# Laser_Array_CPU.net
KiCad netlist of a schematic drawn in EAGLE
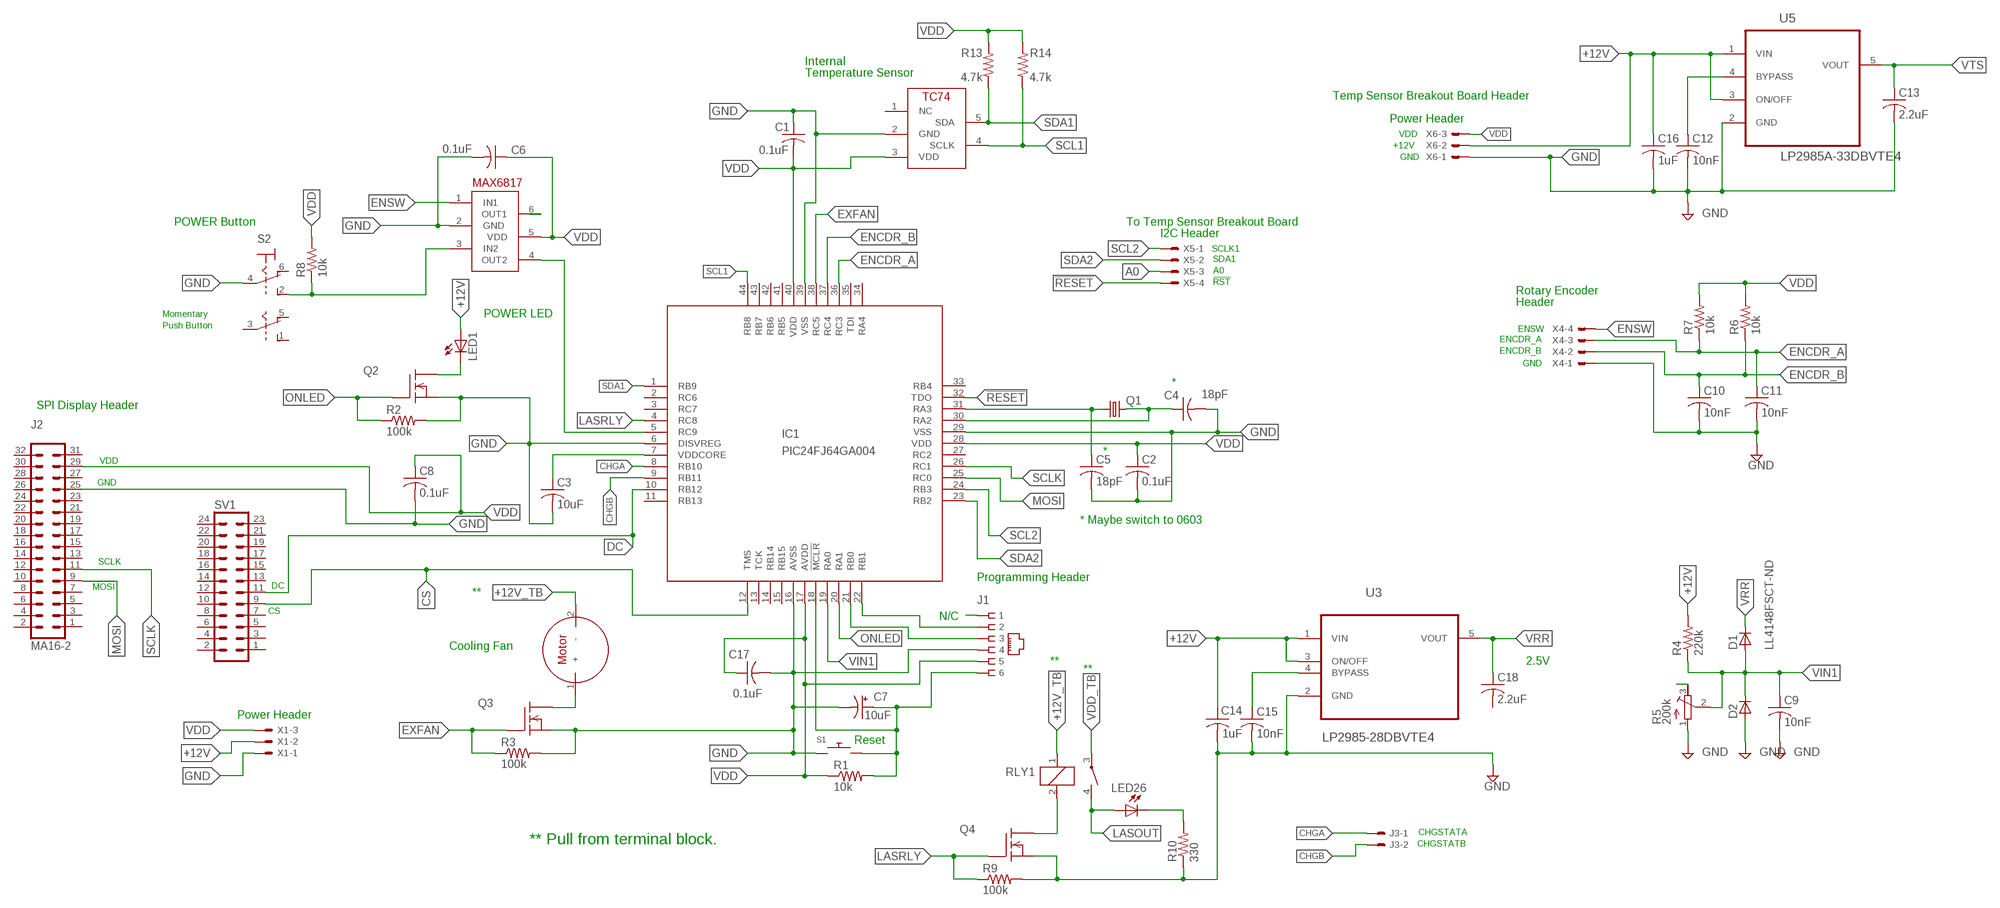
[diagram p0: schematic, sheet 1]

(export (version "E")
  (design (tool "Eeschema 10.0.6"))
  (components
    (comp (ref "C1")
      (value "0.1uF")
      (footprint "eagle-import:C0805")
      (libsource (lib "eagle-import") (part "C-USC0805"))
    )
    (comp (ref "C2")
      (value "0.1uF")
      (footprint "eagle-import:C0805")
      (libsource (lib "eagle-import") (part "C-USC0805"))
    )
    (comp (ref "C3")
      (value "10uF")
      (footprint "eagle-import:C0805")
      (libsource (lib "eagle-import") (part "C-USC0805"))
    )
    (comp (ref "C4")
      (value "18pF")
      (footprint "eagle-import:C0805")
      (libsource (lib "eagle-import") (part "C-USC0805"))
    )
    (comp (ref "C5")
      (value "18pF")
      (footprint "eagle-import:C0805")
      (libsource (lib "eagle-import") (part "C-USC0805"))
    )
    (comp (ref "C6")
      (value "0.1uF")
      (footprint "eagle-import:C0805")
      (libsource (lib "eagle-import") (part "C-USC0805"))
    )
    (comp (ref "C7")
      (value "10uF")
      (footprint "eagle-import:CAP3X3")
      (libsource (lib "eagle-import") (part "CAP3X3"))
    )
    (comp (ref "C8")
      (value "0.1uF")
      (footprint "eagle-import:C0805")
      (libsource (lib "eagle-import") (part "C-USC0805"))
    )
    (comp (ref "C9")
      (value "10nF")
      (footprint "eagle-import:C0805")
      (libsource (lib "eagle-import") (part "C-USC0805"))
    )
    (comp (ref "C10")
      (value "10nF")
      (footprint "eagle-import:C0805")
      (libsource (lib "eagle-import") (part "C-USC0805"))
    )
    (comp (ref "C11")
      (value "10nF")
      (footprint "eagle-import:C0805")
      (libsource (lib "eagle-import") (part "C-USC0805"))
    )
    (comp (ref "C12")
      (value "10nF")
      (footprint "eagle-import:C0805")
      (libsource (lib "eagle-import") (part "C-USC0805"))
    )
    (comp (ref "C13")
      (value "2.2uF")
      (footprint "eagle-import:C0805")
      (libsource (lib "eagle-import") (part "C-USC0805"))
    )
    (comp (ref "C14")
      (value "1uF")
      (footprint "eagle-import:C0805")
      (libsource (lib "eagle-import") (part "C-USC0805"))
    )
    (comp (ref "C15")
      (value "10nF")
      (footprint "eagle-import:C0805")
      (libsource (lib "eagle-import") (part "C-USC0805"))
    )
    (comp (ref "C16")
      (value "1uF")
      (footprint "eagle-import:C0805")
      (libsource (lib "eagle-import") (part "C-USC0805"))
    )
    (comp (ref "C17")
      (value "0.1uF")
      (footprint "eagle-import:C0805")
      (libsource (lib "eagle-import") (part "C-USC0805"))
    )
    (comp (ref "C18")
      (value "2.2uF")
      (footprint "eagle-import:C0805")
      (libsource (lib "eagle-import") (part "C-USC0805"))
    )
    (comp (ref "D1")
      (value "LL4148FSCT-ND")
      (footprint "eagle-import:SOD80")
      (libsource (lib "eagle-import") (part "D-SOD-80"))
    )
    (comp (ref "D2")
      (value "LL4148FSCT-ND")
      (footprint "eagle-import:SOD80")
      (libsource (lib "eagle-import") (part "D-SOD-80"))
    )
    (comp (ref "IC1")
      (value "PIC24FJ64GA004")
      (footprint "eagle-import:TQFP44")
      (fields (field (name "MPN") "PIC24FJ64GA004-E/PT"))
      (libsource (lib "eagle-import") (part "PIC24FJ64GA004"))
    )
    (comp (ref "J1")
      (value "RJ_25")
      (footprint "eagle-import:RJ11-NO_SHIELD")
      (libsource (lib "eagle-import") (part "RJ_25"))
    )
    (comp (ref "J2")
      (value "MA16-2")
      (footprint "eagle-import:MA16-2")
      (libsource (lib "eagle-import") (part "MA16-2"))
    )
    (comp (ref "J3")
      (value "22-23-2021")
      (footprint "eagle-import:22-23-2021")
      (fields (field (name "MF") "MOLEX"))
      (libsource (lib "eagle-import") (part "22-23-2021"))
    )
    (comp (ref "LED1")
      (value "LEDA5MM")
      (footprint "eagle-import:LED5MM")
      (libsource (lib "eagle-import") (part "LEDA5MM"))
    )
    (comp (ref "LED26")
      (value "LEDA5MM")
      (footprint "eagle-import:LED5MM")
      (libsource (lib "eagle-import") (part "LEDA5MM"))
    )
    (comp (ref "M1")
      (value "MOTOR")
      (footprint "eagle-import:22-23-2021")
      (libsource (lib "eagle-import") (part "MOTOR"))
    )
    (comp (ref "Q1")
      (value "CRYSTALSM49")
      (footprint "eagle-import:SM49")
      (libsource (lib "eagle-import") (part "CRYSTALSM49"))
    )
    (comp (ref "Q2")
      (value "QS5U34CT-ND_MOSFET_N_CHANNEL")
      (footprint "eagle-import:SOT23-5L")
      (libsource (lib "eagle-import") (part "QS5U34CT-ND_MOSFET_N_CHANNEL"))
    )
    (comp (ref "Q3")
      (value "QS5U34CT-ND_MOSFET_N_CHANNEL")
      (footprint "eagle-import:SOT23-5L")
      (libsource (lib "eagle-import") (part "QS5U34CT-ND_MOSFET_N_CHANNEL"))
    )
    (comp (ref "Q4")
      (value "QS5U34CT-ND_MOSFET_N_CHANNEL")
      (footprint "eagle-import:SOT23-5L")
      (libsource (lib "eagle-import") (part "QS5U34CT-ND_MOSFET_N_CHANNEL"))
    )
    (comp (ref "R1")
      (value "10k")
      (footprint "eagle-import:R0805")
      (libsource (lib "eagle-import") (part "R-US_R0805"))
    )
    (comp (ref "R2")
      (value "100k")
      (footprint "eagle-import:R0805")
      (libsource (lib "eagle-import") (part "R-US_R0805"))
    )
    (comp (ref "R3")
      (value "100k")
      (footprint "eagle-import:R0805")
      (libsource (lib "eagle-import") (part "R-US_R0805"))
    )
    (comp (ref "R4")
      (value "220k")
      (footprint "eagle-import:M0805")
      (libsource (lib "eagle-import") (part "R-US_M0805"))
    )
    (comp (ref "R5")
      (value "200k")
      (footprint "eagle-import:RTRIM3224X")
      (libsource (lib "eagle-import") (part "R-TRIMM3224X"))
    )
    (comp (ref "R6")
      (value "10k")
      (footprint "eagle-import:M0805")
      (libsource (lib "eagle-import") (part "R-US_M0805"))
    )
    (comp (ref "R7")
      (value "10k")
      (footprint "eagle-import:M0805")
      (libsource (lib "eagle-import") (part "R-US_M0805"))
    )
    (comp (ref "R8")
      (value "10k")
      (footprint "eagle-import:R0805")
      (libsource (lib "eagle-import") (part "R-US_R0805"))
    )
    (comp (ref "R9")
      (value "100k")
      (footprint "eagle-import:R0805")
      (libsource (lib "eagle-import") (part "R-US_R0805"))
    )
    (comp (ref "R10")
      (value "330")
      (footprint "eagle-import:R0805")
      (libsource (lib "eagle-import") (part "R-US_R0805"))
    )
    (comp (ref "R13")
      (value "4.7k")
      (footprint "eagle-import:M0805")
      (libsource (lib "eagle-import") (part "R-US_M0805"))
    )
    (comp (ref "R14")
      (value "4.7k")
      (footprint "eagle-import:M0805")
      (libsource (lib "eagle-import") (part "R-US_M0805"))
    )
    (comp (ref "RLY1")
      (value "RELAY_SPST")
      (footprint "eagle-import:RELAY_SPST")
      (libsource (lib "eagle-import") (part "RELAY_SPST"))
    )
    (comp (ref "S1")
      (value "TACT_PB")
      (footprint "eagle-import:PUSHBUTTON_SMD_SJ")
      (libsource (lib "eagle-import") (part "TACT_PB"))
    )
    (comp (ref "S2")
      (value "DPDT_TOGGLE")
      (footprint "eagle-import:22-23-2061")
      (libsource (lib "eagle-import") (part "DPDT_TOGGLE"))
    )
    (comp (ref "S3")
      (value "TC74")
      (footprint "eagle-import:SOT23-5L")
      (libsource (lib "eagle-import") (part "TC74"))
    )
    (comp (ref "SV1")
      (value "MA12-2")
      (footprint "eagle-import:MA12-2")
      (libsource (lib "eagle-import") (part "MA12-2"))
    )
    (comp (ref "U2")
      (value "MAX6817")
      (footprint "eagle-import:SOT23-6")
      (libsource (lib "eagle-import") (part "MAX6817"))
    )
    (comp (ref "U3")
      (value "LP2985-28DBVTE4")
      (footprint "eagle-import:SOT95P280X145-5N")
      (libsource (lib "eagle-import") (part "LP2985-28DBVTE4"))
    )
    (comp (ref "U5")
      (value "LP2985A-33DBVTE4")
      (footprint "eagle-import:SOT95P280X145-5N")
      (libsource (lib "eagle-import") (part "LP2985A-33DBVTE4"))
    )
    (comp (ref "X1")
      (value "22-23-2031")
      (footprint "eagle-import:22-23-2031")
      (fields (field (name "MF") "MOLEX"))
      (libsource (lib "eagle-import") (part "22-23-2031"))
    )
    (comp (ref "X4")
      (value "22-23-2041")
      (footprint "eagle-import:22-23-2041")
      (fields (field (name "MF") "MOLEX"))
      (libsource (lib "eagle-import") (part "22-23-2041"))
    )
    (comp (ref "X5")
      (value "22-23-2041")
      (footprint "eagle-import:22-23-2041")
      (fields (field (name "MF") "MOLEX"))
      (libsource (lib "eagle-import") (part "22-23-2041"))
    )
    (comp (ref "X6")
      (value "22-23-2031")
      (footprint "eagle-import:22-23-2031")
      (fields (field (name "MF") "MOLEX"))
      (libsource (lib "eagle-import") (part "22-23-2031"))
    )
  )
  (nets
    (net (code "1") (name "+12V") (class "Default")
      (node (ref "C14") (pin "1") (pinfunction "1_1") (pintype "passive"))
      (node (ref "C16") (pin "1") (pinfunction "1_1") (pintype "passive"))
      (node (ref "LED1") (pin "A") (pinfunction "A_A") (pintype "passive"))
      (node (ref "R4") (pin "2") (pinfunction "2_2") (pintype "passive"))
      (node (ref "U3") (pin "1") (pinfunction "VIN_1") (pintype "power_in"))
      (node (ref "U3") (pin "3") (pinfunction "ON/OFF_3") (pintype "input"))
      (node (ref "U5") (pin "1") (pinfunction "VIN_1") (pintype "power_in"))
      (node (ref "U5") (pin "3") (pinfunction "ON/OFF_3") (pintype "input"))
      (node (ref "X1") (pin "2") (pinfunction "S_2") (pintype "passive"))
      (node (ref "X6") (pin "2") (pinfunction "S_2") (pintype "passive"))
    )
    (net (code "2") (name "+12V_TB") (class "Default")
      (node (ref "M1") (pin "2") (pinfunction "-_2") (pintype "bidirectional"))
      (node (ref "RLY1") (pin "1") (pinfunction "1_1") (pintype "passive"))
    )
    (net (code "3") (name "/~{RESET}") (class "Default")
      (node (ref "IC1") (pin "32") (pinfunction "TDO_32") (pintype "output"))
      (node (ref "X5") (pin "4") (pinfunction "S_4") (pintype "passive"))
    )
    (net (code "4") (name "A0") (class "Default")
      (node (ref "X5") (pin "3") (pinfunction "S_3") (pintype "passive"))
    )
    (net (code "5") (name "CHGA") (class "Default")
      (node (ref "IC1") (pin "8") (pinfunction "RB10_8") (pintype "bidirectional"))
      (node (ref "J3") (pin "1") (pinfunction "S_1") (pintype "passive"))
    )
    (net (code "6") (name "CHGB") (class "Default")
      (node (ref "IC1") (pin "9") (pinfunction "RB11_9") (pintype "bidirectional"))
      (node (ref "J3") (pin "2") (pinfunction "S_2") (pintype "passive"))
    )
    (net (code "7") (name "CS") (class "Default")
      (node (ref "IC1") (pin "12") (pinfunction "TMS_12") (pintype "input"))
      (node (ref "SV1") (pin "9") (pinfunction "9_9") (pintype "passive"))
    )
    (net (code "8") (name "DC") (class "Default")
      (node (ref "IC1") (pin "10") (pinfunction "RB12_10") (pintype "bidirectional"))
      (node (ref "SV1") (pin "11") (pinfunction "11_11") (pintype "passive"))
    )
    (net (code "9") (name "ENCDR_A") (class "Default")
      (node (ref "C11") (pin "1") (pinfunction "1_1") (pintype "passive"))
      (node (ref "IC1") (pin "36") (pinfunction "RC3_36") (pintype "bidirectional"))
      (node (ref "R7") (pin "1") (pinfunction "1_1") (pintype "passive"))
      (node (ref "X4") (pin "3") (pinfunction "S_3") (pintype "passive"))
    )
    (net (code "10") (name "ENCDR_B") (class "Default")
      (node (ref "C10") (pin "1") (pinfunction "1_1") (pintype "passive"))
      (node (ref "IC1") (pin "37") (pinfunction "RC4_37") (pintype "bidirectional"))
      (node (ref "R6") (pin "1") (pinfunction "1_1") (pintype "passive"))
      (node (ref "X4") (pin "2") (pinfunction "S_2") (pintype "passive"))
    )
    (net (code "11") (name "ENSW") (class "Default")
      (node (ref "U2") (pin "1") (pinfunction "IN1_1") (pintype "input"))
      (node (ref "X4") (pin "4") (pinfunction "S_4") (pintype "passive"))
    )
    (net (code "12") (name "EXFAN") (class "Default")
      (node (ref "IC1") (pin "38") (pinfunction "RC5_38") (pintype "bidirectional"))
      (node (ref "Q3") (pin "1") (pinfunction "G_1") (pintype "passive"))
      (node (ref "R3") (pin "1") (pinfunction "1_1") (pintype "passive"))
    )
    (net (code "13") (name "GND") (class "Default")
      (node (ref "C1") (pin "1") (pinfunction "1_1") (pintype "passive"))
      (node (ref "C10") (pin "2") (pinfunction "2_2") (pintype "passive"))
      (node (ref "C11") (pin "2") (pinfunction "2_2") (pintype "passive"))
      (node (ref "C12") (pin "2") (pinfunction "2_2") (pintype "passive"))
      (node (ref "C13") (pin "2") (pinfunction "2_2") (pintype "passive"))
      (node (ref "C14") (pin "2") (pinfunction "2_2") (pintype "passive"))
      (node (ref "C15") (pin "2") (pinfunction "2_2") (pintype "passive"))
      (node (ref "C16") (pin "2") (pinfunction "2_2") (pintype "passive"))
      (node (ref "C17") (pin "2") (pinfunction "2_2") (pintype "passive"))
      (node (ref "C2") (pin "2") (pinfunction "2_2") (pintype "passive"))
      (node (ref "C3") (pin "2") (pinfunction "2_2") (pintype "passive"))
      (node (ref "C4") (pin "2") (pinfunction "2_2") (pintype "passive"))
      (node (ref "C5") (pin "2") (pinfunction "2_2") (pintype "passive"))
      (node (ref "C6") (pin "2") (pinfunction "2_2") (pintype "passive"))
      (node (ref "C7") (pin "-") (pinfunction "-_-") (pintype "passive"))
      (node (ref "C8") (pin "2") (pinfunction "2_2") (pintype "passive"))
      (node (ref "C9") (pin "2") (pinfunction "2_2") (pintype "passive"))
      (node (ref "D2") (pin "2") (pinfunction "A_2") (pintype "passive"))
      (node (ref "IC1") (pin "16") (pinfunction "AVSS_16") (pintype "power_in"))
      (node (ref "IC1") (pin "29") (pinfunction "VSS_29") (pintype "power_in"))
      (node (ref "IC1") (pin "39") (pinfunction "VSS_39") (pintype "power_in"))
      (node (ref "IC1") (pin "6") (pinfunction "DISVREG_6") (pintype "passive"))
      (node (ref "J1") (pin "4") (pinfunction "4_4") (pintype "passive"))
      (node (ref "J2") (pin "25") (pinfunction "25_25") (pintype "passive"))
      (node (ref "Q2") (pin "2") (pinfunction "S_2") (pintype "passive"))
      (node (ref "Q3") (pin "2") (pinfunction "S_2") (pintype "passive"))
      (node (ref "Q4") (pin "2") (pinfunction "S_2") (pintype "passive"))
      (node (ref "R10") (pin "1") (pinfunction "1_1") (pintype "passive"))
      (node (ref "R2") (pin "2") (pinfunction "2_2") (pintype "passive"))
      (node (ref "R3") (pin "2") (pinfunction "2_2") (pintype "passive"))
      (node (ref "R5") (pin "1") (pinfunction "A_1") (pintype "passive"))
      (node (ref "R9") (pin "2") (pinfunction "2_2") (pintype "passive"))
      (node (ref "S1") (pin "1") (pinfunction "1_1") (pintype "passive"))
      (node (ref "S1") (pin "2") (pinfunction "1_2") (pintype "passive"))
      (node (ref "S2") (pin "4") (pinfunction "P_4") (pintype "passive"))
      (node (ref "S3") (pin "2") (pinfunction "GND_2") (pintype "bidirectional"))
      (node (ref "U2") (pin "2") (pinfunction "GND_2") (pintype "power_in"))
      (node (ref "U3") (pin "2") (pinfunction "GND_2") (pintype "passive"))
      (node (ref "U5") (pin "2") (pinfunction "GND_2") (pintype "passive"))
      (node (ref "X1") (pin "1") (pinfunction "S_1") (pintype "passive"))
      (node (ref "X4") (pin "1") (pinfunction "S_1") (pintype "passive"))
      (node (ref "X6") (pin "1") (pinfunction "S_1") (pintype "passive"))
    )
    (net (code "14") (name "LASOUT") (class "Default")
      (node (ref "LED26") (pin "A") (pinfunction "A_A") (pintype "passive"))
      (node (ref "RLY1") (pin "4") (pinfunction "S_4") (pintype "passive"))
    )
    (net (code "15") (name "LASRLY") (class "Default")
      (node (ref "IC1") (pin "4") (pinfunction "RC8_4") (pintype "bidirectional"))
      (node (ref "Q4") (pin "1") (pinfunction "G_1") (pintype "passive"))
      (node (ref "R9") (pin "1") (pinfunction "1_1") (pintype "passive"))
    )
    (net (code "16") (name "MOSI") (class "Default")
      (node (ref "IC1") (pin "25") (pinfunction "RC0_25") (pintype "bidirectional"))
      (node (ref "J2") (pin "9") (pinfunction "9_9") (pintype "passive"))
    )
    (net (code "17") (name "Net-(IC1-RA2)") (class "Default")
      (node (ref "C4") (pin "1") (pinfunction "1_1") (pintype "passive"))
      (node (ref "IC1") (pin "30") (pinfunction "RA2_30") (pintype "bidirectional"))
      (node (ref "Q1") (pin "2") (pinfunction "2_2") (pintype "passive"))
    )
    (net (code "18") (name "Net-(IC1-RA3)") (class "Default")
      (node (ref "C5") (pin "1") (pinfunction "1_1") (pintype "passive"))
      (node (ref "IC1") (pin "31") (pinfunction "RA3_31") (pintype "bidirectional"))
      (node (ref "Q1") (pin "1") (pinfunction "1_1") (pintype "passive"))
    )
    (net (code "19") (name "Net-(IC1-RB0)") (class "Default")
      (node (ref "IC1") (pin "21") (pinfunction "RB0_21") (pintype "bidirectional"))
      (node (ref "J1") (pin "3") (pinfunction "3_3") (pintype "passive"))
    )
    (net (code "20") (name "Net-(IC1-RB1)") (class "Default")
      (node (ref "IC1") (pin "22") (pinfunction "RB1_22") (pintype "bidirectional"))
      (node (ref "J1") (pin "2") (pinfunction "2_2") (pintype "passive"))
    )
    (net (code "21") (name "Net-(IC1-RC9)") (class "Default")
      (node (ref "IC1") (pin "5") (pinfunction "RC9_5") (pintype "bidirectional"))
      (node (ref "U2") (pin "4") (pinfunction "OUT2_4") (pintype "output"))
    )
    (net (code "22") (name "Net-(IC1-VDDCORE)") (class "Default")
      (node (ref "C3") (pin "1") (pinfunction "1_1") (pintype "passive"))
      (node (ref "IC1") (pin "7") (pinfunction "VDDCORE_7") (pintype "power_in"))
    )
    (net (code "23") (name "Net-(IC1-~{MCLR})") (class "Default")
      (node (ref "C7") (pin "+") (pinfunction "+_+") (pintype "passive"))
      (node (ref "IC1") (pin "18") (pinfunction "~{MCLR}_18") (pintype "bidirectional"))
      (node (ref "J1") (pin "6") (pinfunction "6_6") (pintype "passive"))
      (node (ref "R1") (pin "2") (pinfunction "2_2") (pintype "passive"))
      (node (ref "S1") (pin "3") (pinfunction "2_3") (pintype "passive"))
      (node (ref "S1") (pin "4") (pinfunction "2_4") (pintype "passive"))
    )
    (net (code "24") (name "Net-(LED1-C)") (class "Default")
      (node (ref "LED1") (pin "K") (pinfunction "C_K") (pintype "passive"))
      (node (ref "Q2") (pin "5") (pinfunction "D_5") (pintype "passive"))
    )
    (net (code "25") (name "Net-(LED26-C)") (class "Default")
      (node (ref "LED26") (pin "K") (pinfunction "C_K") (pintype "passive"))
      (node (ref "R10") (pin "2") (pinfunction "2_2") (pintype "passive"))
    )
    (net (code "26") (name "Net-(M1-+)") (class "Default")
      (node (ref "M1") (pin "1") (pinfunction "+_1") (pintype "bidirectional"))
      (node (ref "Q3") (pin "5") (pinfunction "D_5") (pintype "passive"))
    )
    (net (code "27") (name "Net-(Q4-D)") (class "Default")
      (node (ref "Q4") (pin "5") (pinfunction "D_5") (pintype "passive"))
      (node (ref "RLY1") (pin "2") (pinfunction "2_2") (pintype "passive"))
    )
    (net (code "28") (name "Net-(S2-S)") (class "Default")
      (node (ref "R8") (pin "1") (pinfunction "1_1") (pintype "passive"))
      (node (ref "S2") (pin "2") (pinfunction "S_2") (pintype "passive"))
      (node (ref "U2") (pin "3") (pinfunction "IN2_3") (pintype "input"))
    )
    (net (code "29") (name "Net-(U3-BYPASS)") (class "Default")
      (node (ref "C15") (pin "1") (pinfunction "1_1") (pintype "passive"))
      (node (ref "U3") (pin "4") (pinfunction "BYPASS_4") (pintype "input"))
    )
    (net (code "30") (name "Net-(U5-BYPASS)") (class "Default")
      (node (ref "C12") (pin "1") (pinfunction "1_1") (pintype "passive"))
      (node (ref "U5") (pin "4") (pinfunction "BYPASS_4") (pintype "input"))
    )
    (net (code "31") (name "ONLED") (class "Default")
      (node (ref "IC1") (pin "20") (pinfunction "RA1_20") (pintype "bidirectional"))
      (node (ref "Q2") (pin "1") (pinfunction "G_1") (pintype "passive"))
      (node (ref "R2") (pin "1") (pinfunction "1_1") (pintype "passive"))
    )
    (net (code "32") (name "SCL1") (class "Default")
      (node (ref "IC1") (pin "44") (pinfunction "RB8_44") (pintype "bidirectional"))
      (node (ref "R14") (pin "1") (pinfunction "1_1") (pintype "passive"))
      (node (ref "S3") (pin "4") (pinfunction "SCLK_4") (pintype "bidirectional"))
    )
    (net (code "33") (name "SCL2") (class "Default")
      (node (ref "IC1") (pin "24") (pinfunction "RB3_24") (pintype "bidirectional"))
      (node (ref "X5") (pin "1") (pinfunction "S_1") (pintype "passive"))
    )
    (net (code "34") (name "SCLK") (class "Default")
      (node (ref "IC1") (pin "26") (pinfunction "RC1_26") (pintype "bidirectional"))
      (node (ref "J2") (pin "11") (pinfunction "11_11") (pintype "passive"))
    )
    (net (code "35") (name "SDA1") (class "Default")
      (node (ref "IC1") (pin "1") (pinfunction "RB9_1") (pintype "bidirectional"))
      (node (ref "R13") (pin "1") (pinfunction "1_1") (pintype "passive"))
      (node (ref "S3") (pin "5") (pinfunction "SDA_5") (pintype "bidirectional"))
    )
    (net (code "36") (name "SDA2") (class "Default")
      (node (ref "IC1") (pin "23") (pinfunction "RB2_23") (pintype "bidirectional"))
      (node (ref "X5") (pin "2") (pinfunction "S_2") (pintype "passive"))
    )
    (net (code "37") (name "VDD") (class "Default")
      (node (ref "C1") (pin "2") (pinfunction "2_2") (pintype "passive"))
      (node (ref "C17") (pin "1") (pinfunction "1_1") (pintype "passive"))
      (node (ref "C2") (pin "1") (pinfunction "1_1") (pintype "passive"))
      (node (ref "C6") (pin "1") (pinfunction "1_1") (pintype "passive"))
      (node (ref "C8") (pin "1") (pinfunction "1_1") (pintype "passive"))
      (node (ref "IC1") (pin "17") (pinfunction "AVDD_17") (pintype "power_in"))
      (node (ref "IC1") (pin "28") (pinfunction "VDD_28") (pintype "power_in"))
      (node (ref "IC1") (pin "40") (pinfunction "VDD_40") (pintype "power_in"))
      (node (ref "J1") (pin "5") (pinfunction "5_5") (pintype "passive"))
      (node (ref "J2") (pin "29") (pinfunction "29_29") (pintype "passive"))
      (node (ref "R1") (pin "1") (pinfunction "1_1") (pintype "passive"))
      (node (ref "R13") (pin "2") (pinfunction "2_2") (pintype "passive"))
      (node (ref "R14") (pin "2") (pinfunction "2_2") (pintype "passive"))
      (node (ref "R6") (pin "2") (pinfunction "2_2") (pintype "passive"))
      (node (ref "R7") (pin "2") (pinfunction "2_2") (pintype "passive"))
      (node (ref "R8") (pin "2") (pinfunction "2_2") (pintype "passive"))
      (node (ref "S3") (pin "3") (pinfunction "VDD_3") (pintype "bidirectional"))
      (node (ref "U2") (pin "5") (pinfunction "VDD_5") (pintype "power_in"))
      (node (ref "X1") (pin "3") (pinfunction "S_3") (pintype "passive"))
      (node (ref "X6") (pin "3") (pinfunction "S_3") (pintype "passive"))
    )
    (net (code "38") (name "VDD_TB") (class "Default")
      (node (ref "RLY1") (pin "3") (pinfunction "P_3") (pintype "passive"))
    )
    (net (code "39") (name "VIN1") (class "Default")
      (node (ref "C9") (pin "1") (pinfunction "1_1") (pintype "passive"))
      (node (ref "D1") (pin "2") (pinfunction "A_2") (pintype "passive"))
      (node (ref "D2") (pin "1") (pinfunction "C_1") (pintype "passive"))
      (node (ref "IC1") (pin "19") (pinfunction "RA0_19") (pintype "bidirectional"))
      (node (ref "R4") (pin "1") (pinfunction "1_1") (pintype "passive"))
      (node (ref "R5") (pin "2") (pinfunction "S_2") (pintype "passive"))
    )
    (net (code "40") (name "VRR") (class "Default")
      (node (ref "C18") (pin "1") (pinfunction "1_1") (pintype "passive"))
      (node (ref "D1") (pin "1") (pinfunction "C_1") (pintype "passive"))
      (node (ref "U3") (pin "5") (pinfunction "VOUT_5") (pintype "output"))
    )
    (net (code "41") (name "VTS") (class "Default")
      (node (ref "C13") (pin "1") (pinfunction "1_1") (pintype "passive"))
      (node (ref "U5") (pin "5") (pinfunction "VOUT_5") (pintype "output"))
    )
    (net (code "42") (name "unconnected-(C18-Pad2)") (class "Default")
      (node (ref "C18") (pin "2") (pinfunction "2_2") (pintype "passive"))
    )
    (net (code "43") (name "unconnected-(IC1-RA4-Pad34)") (class "Default")
      (node (ref "IC1") (pin "34") (pinfunction "RA4_34") (pintype "bidirectional"))
    )
    (net (code "44") (name "unconnected-(IC1-RB4-Pad33)") (class "Default")
      (node (ref "IC1") (pin "33") (pinfunction "RB4_33") (pintype "bidirectional"))
    )
    (net (code "45") (name "unconnected-(IC1-RB5-Pad41)") (class "Default")
      (node (ref "IC1") (pin "41") (pinfunction "RB5_41") (pintype "bidirectional"))
    )
    (net (code "46") (name "unconnected-(IC1-RB6-Pad42)") (class "Default")
      (node (ref "IC1") (pin "42") (pinfunction "RB6_42") (pintype "bidirectional"))
    )
    (net (code "47") (name "unconnected-(IC1-RB7-Pad43)") (class "Default")
      (node (ref "IC1") (pin "43") (pinfunction "RB7_43") (pintype "bidirectional"))
    )
    (net (code "48") (name "unconnected-(IC1-RB13-Pad11)") (class "Default")
      (node (ref "IC1") (pin "11") (pinfunction "RB13_11") (pintype "bidirectional"))
    )
    (net (code "49") (name "unconnected-(IC1-RB14-Pad14)") (class "Default")
      (node (ref "IC1") (pin "14") (pinfunction "RB14_14") (pintype "bidirectional"))
    )
    (net (code "50") (name "unconnected-(IC1-RB15-Pad15)") (class "Default")
      (node (ref "IC1") (pin "15") (pinfunction "RB15_15") (pintype "bidirectional"))
    )
    (net (code "51") (name "unconnected-(IC1-RC2-Pad27)") (class "Default")
      (node (ref "IC1") (pin "27") (pinfunction "RC2_27") (pintype "bidirectional"))
    )
    (net (code "52") (name "unconnected-(IC1-RC6-Pad2)") (class "Default")
      (node (ref "IC1") (pin "2") (pinfunction "RC6_2") (pintype "bidirectional"))
    )
    (net (code "53") (name "unconnected-(IC1-RC7-Pad3)") (class "Default")
      (node (ref "IC1") (pin "3") (pinfunction "RC7_3") (pintype "bidirectional"))
    )
    (net (code "54") (name "unconnected-(IC1-TCK-Pad13)") (class "Default")
      (node (ref "IC1") (pin "13") (pinfunction "TCK_13") (pintype "input"))
    )
    (net (code "55") (name "unconnected-(IC1-TDI-Pad35)") (class "Default")
      (node (ref "IC1") (pin "35") (pinfunction "TDI_35") (pintype "input"))
    )
    (net (code "56") (name "unconnected-(J1-Pad1)") (class "Default")
      (node (ref "J1") (pin "1") (pinfunction "1_1") (pintype "passive"))
    )
    (net (code "57") (name "unconnected-(J2-Pad1)") (class "Default")
      (node (ref "J2") (pin "1") (pinfunction "1_1") (pintype "passive"))
    )
    (net (code "58") (name "unconnected-(J2-Pad2)") (class "Default")
      (node (ref "J2") (pin "2") (pinfunction "2_2") (pintype "passive"))
    )
    (net (code "59") (name "unconnected-(J2-Pad3)") (class "Default")
      (node (ref "J2") (pin "3") (pinfunction "3_3") (pintype "passive"))
    )
    (net (code "60") (name "unconnected-(J2-Pad4)") (class "Default")
      (node (ref "J2") (pin "4") (pinfunction "4_4") (pintype "passive"))
    )
    (net (code "61") (name "unconnected-(J2-Pad5)") (class "Default")
      (node (ref "J2") (pin "5") (pinfunction "5_5") (pintype "passive"))
    )
    (net (code "62") (name "unconnected-(J2-Pad6)") (class "Default")
      (node (ref "J2") (pin "6") (pinfunction "6_6") (pintype "passive"))
    )
    (net (code "63") (name "unconnected-(J2-Pad7)") (class "Default")
      (node (ref "J2") (pin "7") (pinfunction "7_7") (pintype "passive"))
    )
    (net (code "64") (name "unconnected-(J2-Pad8)") (class "Default")
      (node (ref "J2") (pin "8") (pinfunction "8_8") (pintype "passive"))
    )
    (net (code "65") (name "unconnected-(J2-Pad10)") (class "Default")
      (node (ref "J2") (pin "10") (pinfunction "10_10") (pintype "passive"))
    )
    (net (code "66") (name "unconnected-(J2-Pad12)") (class "Default")
      (node (ref "J2") (pin "12") (pinfunction "12_12") (pintype "passive"))
    )
    (net (code "67") (name "unconnected-(J2-Pad13)") (class "Default")
      (node (ref "J2") (pin "13") (pinfunction "13_13") (pintype "passive"))
    )
    (net (code "68") (name "unconnected-(J2-Pad14)") (class "Default")
      (node (ref "J2") (pin "14") (pinfunction "14_14") (pintype "passive"))
    )
    (net (code "69") (name "unconnected-(J2-Pad15)") (class "Default")
      (node (ref "J2") (pin "15") (pinfunction "15_15") (pintype "passive"))
    )
    (net (code "70") (name "unconnected-(J2-Pad16)") (class "Default")
      (node (ref "J2") (pin "16") (pinfunction "16_16") (pintype "passive"))
    )
    (net (code "71") (name "unconnected-(J2-Pad17)") (class "Default")
      (node (ref "J2") (pin "17") (pinfunction "17_17") (pintype "passive"))
    )
    (net (code "72") (name "unconnected-(J2-Pad18)") (class "Default")
      (node (ref "J2") (pin "18") (pinfunction "18_18") (pintype "passive"))
    )
    (net (code "73") (name "unconnected-(J2-Pad19)") (class "Default")
      (node (ref "J2") (pin "19") (pinfunction "19_19") (pintype "passive"))
    )
    (net (code "74") (name "unconnected-(J2-Pad20)") (class "Default")
      (node (ref "J2") (pin "20") (pinfunction "20_20") (pintype "passive"))
    )
    (net (code "75") (name "unconnected-(J2-Pad21)") (class "Default")
      (node (ref "J2") (pin "21") (pinfunction "21_21") (pintype "passive"))
    )
    (net (code "76") (name "unconnected-(J2-Pad22)") (class "Default")
      (node (ref "J2") (pin "22") (pinfunction "22_22") (pintype "passive"))
    )
    (net (code "77") (name "unconnected-(J2-Pad23)") (class "Default")
      (node (ref "J2") (pin "23") (pinfunction "23_23") (pintype "passive"))
    )
    (net (code "78") (name "unconnected-(J2-Pad24)") (class "Default")
      (node (ref "J2") (pin "24") (pinfunction "24_24") (pintype "passive"))
    )
    (net (code "79") (name "unconnected-(J2-Pad26)") (class "Default")
      (node (ref "J2") (pin "26") (pinfunction "26_26") (pintype "passive"))
    )
    (net (code "80") (name "unconnected-(J2-Pad27)") (class "Default")
      (node (ref "J2") (pin "27") (pinfunction "27_27") (pintype "passive"))
    )
    (net (code "81") (name "unconnected-(J2-Pad28)") (class "Default")
      (node (ref "J2") (pin "28") (pinfunction "28_28") (pintype "passive"))
    )
    (net (code "82") (name "unconnected-(J2-Pad30)") (class "Default")
      (node (ref "J2") (pin "30") (pinfunction "30_30") (pintype "passive"))
    )
    (net (code "83") (name "unconnected-(J2-Pad31)") (class "Default")
      (node (ref "J2") (pin "31") (pinfunction "31_31") (pintype "passive"))
    )
    (net (code "84") (name "unconnected-(J2-Pad32)") (class "Default")
      (node (ref "J2") (pin "32") (pinfunction "32_32") (pintype "passive"))
    )
    (net (code "85") (name "unconnected-(R5-E-Pad3)") (class "Default")
      (node (ref "R5") (pin "3") (pinfunction "E_3") (pintype "passive"))
    )
    (net (code "86") (name "unconnected-(S2-O-Pad6)") (class "Default")
      (node (ref "S2") (pin "6") (pinfunction "O_6") (pintype "passive"))
    )
    (net (code "87") (name "unconnected-(S2-O1-Pad5)") (class "Default")
      (node (ref "S2") (pin "5") (pinfunction "O1_5") (pintype "passive"))
    )
    (net (code "88") (name "unconnected-(S2-P1-Pad3)") (class "Default")
      (node (ref "S2") (pin "3") (pinfunction "P1_3") (pintype "passive"))
    )
    (net (code "89") (name "unconnected-(S2-S1-Pad1)") (class "Default")
      (node (ref "S2") (pin "1") (pinfunction "S1_1") (pintype "passive"))
    )
    (net (code "90") (name "unconnected-(S3-NC-Pad1)") (class "Default")
      (node (ref "S3") (pin "1") (pinfunction "NC_1") (pintype "bidirectional"))
    )
    (net (code "91") (name "unconnected-(SV1-Pad1)") (class "Default")
      (node (ref "SV1") (pin "1") (pinfunction "1_1") (pintype "passive"))
    )
    (net (code "92") (name "unconnected-(SV1-Pad2)") (class "Default")
      (node (ref "SV1") (pin "2") (pinfunction "2_2") (pintype "passive"))
    )
    (net (code "93") (name "unconnected-(SV1-Pad3)") (class "Default")
      (node (ref "SV1") (pin "3") (pinfunction "3_3") (pintype "passive"))
    )
    (net (code "94") (name "unconnected-(SV1-Pad4)") (class "Default")
      (node (ref "SV1") (pin "4") (pinfunction "4_4") (pintype "passive"))
    )
    (net (code "95") (name "unconnected-(SV1-Pad5)") (class "Default")
      (node (ref "SV1") (pin "5") (pinfunction "5_5") (pintype "passive"))
    )
    (net (code "96") (name "unconnected-(SV1-Pad6)") (class "Default")
      (node (ref "SV1") (pin "6") (pinfunction "6_6") (pintype "passive"))
    )
    (net (code "97") (name "unconnected-(SV1-Pad7)") (class "Default")
      (node (ref "SV1") (pin "7") (pinfunction "7_7") (pintype "passive"))
    )
    (net (code "98") (name "unconnected-(SV1-Pad8)") (class "Default")
      (node (ref "SV1") (pin "8") (pinfunction "8_8") (pintype "passive"))
    )
    (net (code "99") (name "unconnected-(SV1-Pad10)") (class "Default")
      (node (ref "SV1") (pin "10") (pinfunction "10_10") (pintype "passive"))
    )
    (net (code "100") (name "unconnected-(SV1-Pad12)") (class "Default")
      (node (ref "SV1") (pin "12") (pinfunction "12_12") (pintype "passive"))
    )
    (net (code "101") (name "unconnected-(SV1-Pad13)") (class "Default")
      (node (ref "SV1") (pin "13") (pinfunction "13_13") (pintype "passive"))
    )
    (net (code "102") (name "unconnected-(SV1-Pad14)") (class "Default")
      (node (ref "SV1") (pin "14") (pinfunction "14_14") (pintype "passive"))
    )
    (net (code "103") (name "unconnected-(SV1-Pad15)") (class "Default")
      (node (ref "SV1") (pin "15") (pinfunction "15_15") (pintype "passive"))
    )
    (net (code "104") (name "unconnected-(SV1-Pad16)") (class "Default")
      (node (ref "SV1") (pin "16") (pinfunction "16_16") (pintype "passive"))
    )
    (net (code "105") (name "unconnected-(SV1-Pad17)") (class "Default")
      (node (ref "SV1") (pin "17") (pinfunction "17_17") (pintype "passive"))
    )
    (net (code "106") (name "unconnected-(SV1-Pad18)") (class "Default")
      (node (ref "SV1") (pin "18") (pinfunction "18_18") (pintype "passive"))
    )
    (net (code "107") (name "unconnected-(SV1-Pad19)") (class "Default")
      (node (ref "SV1") (pin "19") (pinfunction "19_19") (pintype "passive"))
    )
    (net (code "108") (name "unconnected-(SV1-Pad20)") (class "Default")
      (node (ref "SV1") (pin "20") (pinfunction "20_20") (pintype "passive"))
    )
    (net (code "109") (name "unconnected-(SV1-Pad21)") (class "Default")
      (node (ref "SV1") (pin "21") (pinfunction "21_21") (pintype "passive"))
    )
    (net (code "110") (name "unconnected-(SV1-Pad22)") (class "Default")
      (node (ref "SV1") (pin "22") (pinfunction "22_22") (pintype "passive"))
    )
    (net (code "111") (name "unconnected-(SV1-Pad23)") (class "Default")
      (node (ref "SV1") (pin "23") (pinfunction "23_23") (pintype "passive"))
    )
    (net (code "112") (name "unconnected-(SV1-Pad24)") (class "Default")
      (node (ref "SV1") (pin "24") (pinfunction "24_24") (pintype "passive"))
    )
    (net (code "113") (name "unconnected-(U2-OUT1-Pad6)") (class "Default")
      (node (ref "U2") (pin "6") (pinfunction "OUT1_6") (pintype "output"))
    )
  )
)
